# MKL02_Programmer.net
KiCad netlist of a schematic drawn in EAGLE
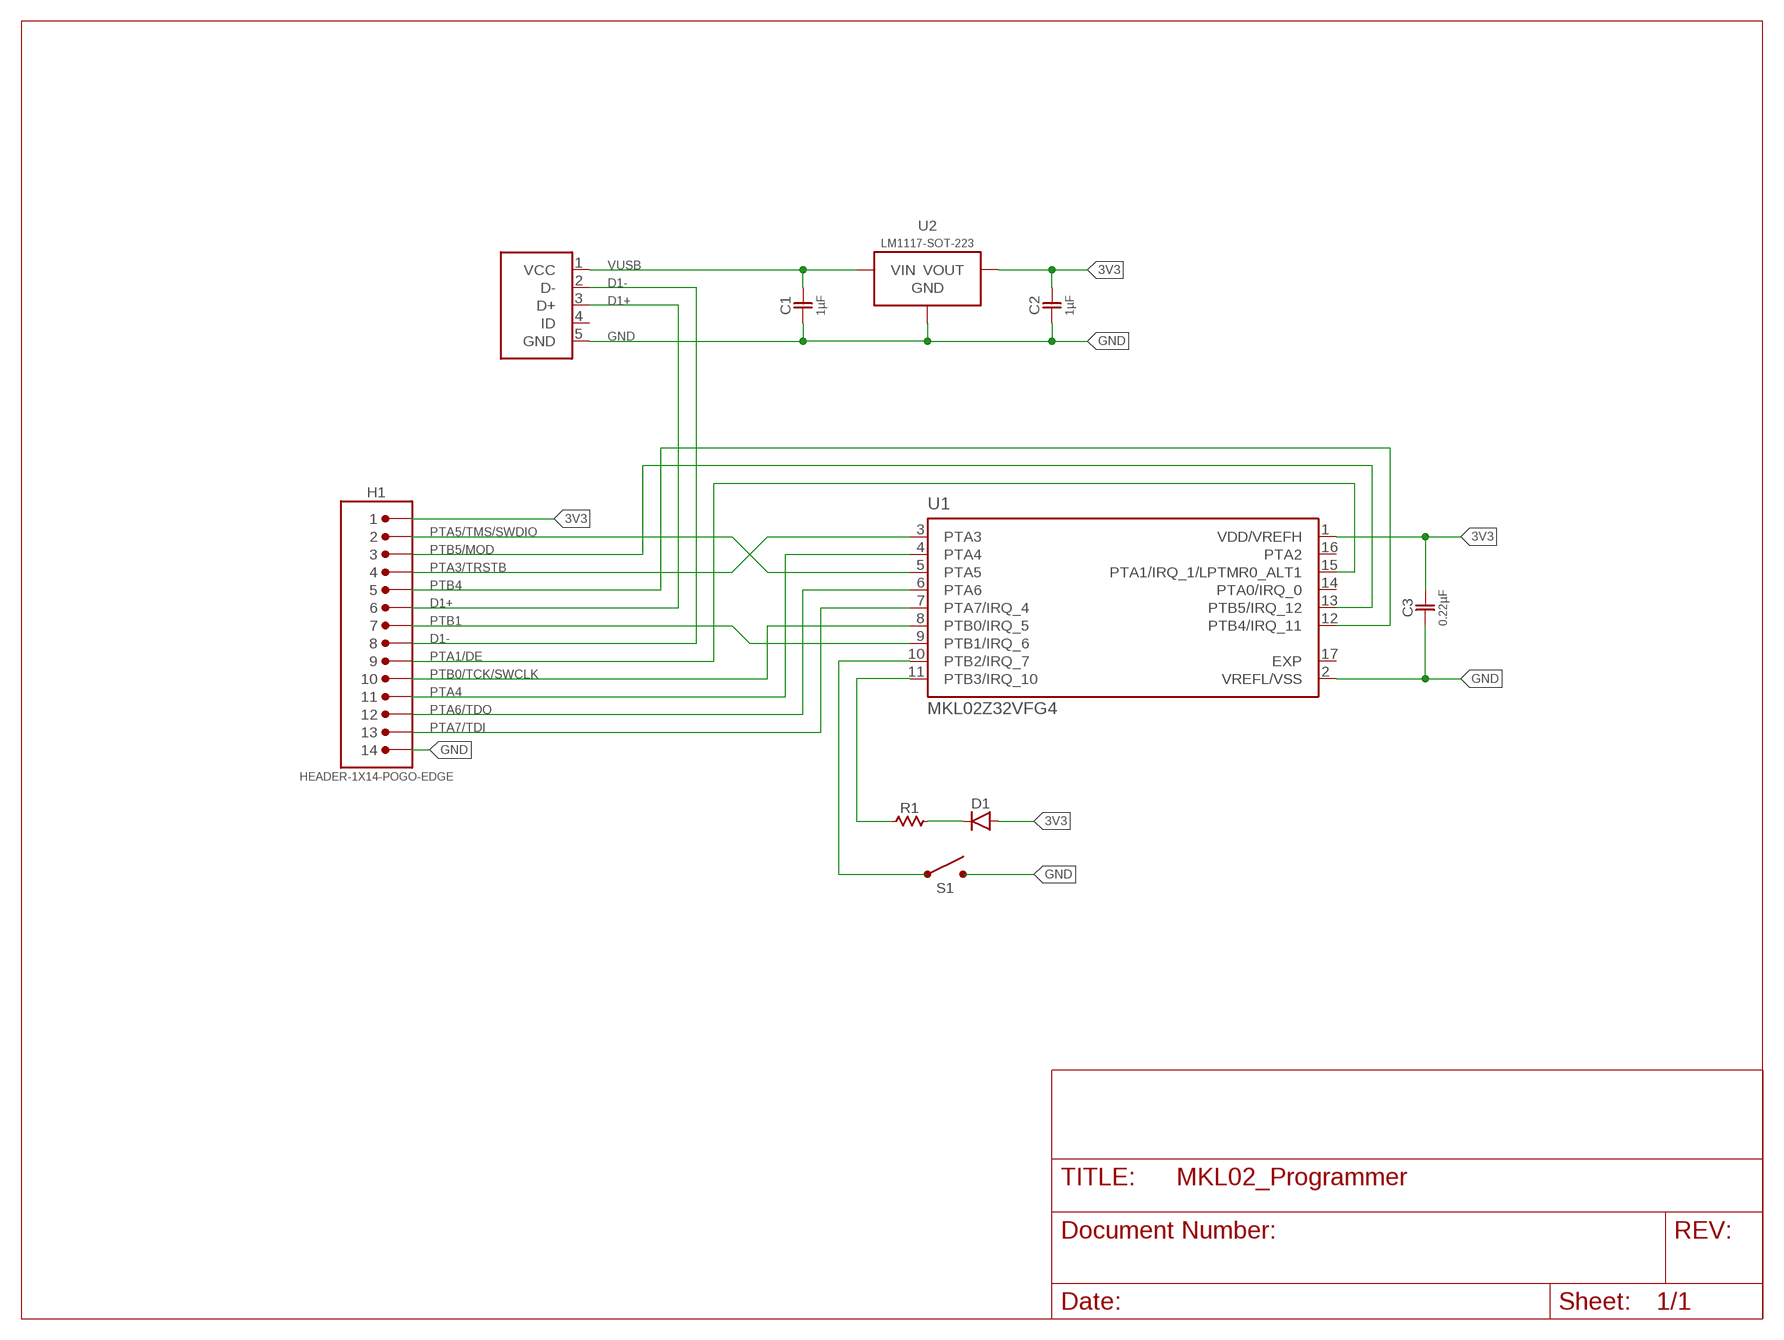
[diagram p0: schematic, sheet 1]

(export (version "E")
  (design (tool "Eeschema 10.0.6"))
  (components
    (comp (ref "C1")
      (value "1µF")
      (footprint "eagle-import:0805-NP")
      (libsource (lib "eagle-import") (part "CAP-NP-0805"))
    )
    (comp (ref "C2")
      (value "1µF")
      (footprint "eagle-import:0805-NP")
      (libsource (lib "eagle-import") (part "CAP-NP-0805"))
    )
    (comp (ref "C3")
      (value "0.22µF")
      (footprint "eagle-import:0805-NP")
      (libsource (lib "eagle-import") (part "CAP-NP-0805"))
    )
    (comp (ref "D1")
      (value "DIODE-0805")
      (footprint "eagle-import:0805-P")
      (libsource (lib "eagle-import") (part "DIODE-0805"))
    )
    (comp (ref "H1")
      (value "HEADER-1X14-POGO-EDGE")
      (footprint "eagle-import:2X7-1.27MM-POGO-EDGE")
      (libsource (lib "eagle-import") (part "HEADER-1X14-POGO-EDGE"))
    )
    (comp (ref "J1")
      (value "USB-5-MICRO-B")
      (footprint "eagle-import:USB-MICRO-B")
      (libsource (lib "eagle-import") (part "USB-5-MICRO-B"))
    )
    (comp (ref "R1")
      (value "RESISTOR-0805")
      (footprint "eagle-import:0805-NP")
      (libsource (lib "eagle-import") (part "RESISTOR-0805"))
    )
    (comp (ref "S1")
      (value "SPST-6X6")
      (footprint "eagle-import:BUTTON-EVQQ2")
      (libsource (lib "eagle-import") (part "SPST-6X6"))
    )
    (comp (ref "U1")
      (value "MKL02Z32VFG4")
      (footprint "eagle-import:QFN50P300X300X65-17N")
      (fields (field (name "DIGI-KEY_PART_NUMBER") "MKL02Z32VFG4-ND") (field (name "MF") "NXP USA"))
      (libsource (lib "eagle-import") (part "MKL02Z32VFG4"))
    )
    (comp (ref "U2")
      (value "LM1117-SOT-223")
      (footprint "eagle-import:SOT-223")
      (libsource (lib "eagle-import") (part "LM1117-SOT-223"))
    )
  )
  (nets
    (net (code "1") (name "/D1+") (class "Default")
      (node (ref "H1") (pin "6") (pinfunction "6_6") (pintype "bidirectional"))
      (node (ref "J1") (pin "3") (pinfunction "D+_3") (pintype "bidirectional"))
    )
    (net (code "2") (name "/D1-") (class "Default")
      (node (ref "H1") (pin "8") (pinfunction "8_8") (pintype "bidirectional"))
      (node (ref "J1") (pin "2") (pinfunction "D-_2") (pintype "bidirectional"))
    )
    (net (code "3") (name "/EXP") (class "Default")
      (node (ref "U1") (pin "17") (pinfunction "EXP_17") (pintype "power_in"))
    )
    (net (code "4") (name "/PTA1{slash}DE") (class "Default")
      (node (ref "H1") (pin "9") (pinfunction "9_9") (pintype "bidirectional"))
      (node (ref "U1") (pin "15") (pinfunction "PTA1/IRQ_1/LPTMR0_ALT1_15") (pintype "bidirectional"))
    )
    (net (code "5") (name "/PTA3{slash}TRSTB") (class "Default")
      (node (ref "H1") (pin "4") (pinfunction "4_4") (pintype "bidirectional"))
      (node (ref "U1") (pin "3") (pinfunction "PTA3_3") (pintype "bidirectional"))
    )
    (net (code "6") (name "/PTA4") (class "Default")
      (node (ref "H1") (pin "11") (pinfunction "11_11") (pintype "bidirectional"))
      (node (ref "U1") (pin "4") (pinfunction "PTA4_4") (pintype "bidirectional"))
    )
    (net (code "7") (name "/PTA5{slash}TMS{slash}SWDIO") (class "Default")
      (node (ref "H1") (pin "2") (pinfunction "2_2") (pintype "bidirectional"))
      (node (ref "U1") (pin "5") (pinfunction "PTA5_5") (pintype "bidirectional"))
    )
    (net (code "8") (name "/PTA6{slash}TDO") (class "Default")
      (node (ref "H1") (pin "12") (pinfunction "12_12") (pintype "bidirectional"))
      (node (ref "U1") (pin "6") (pinfunction "PTA6_6") (pintype "bidirectional"))
    )
    (net (code "9") (name "/PTA7{slash}TDI") (class "Default")
      (node (ref "H1") (pin "13") (pinfunction "13_13") (pintype "bidirectional"))
      (node (ref "U1") (pin "7") (pinfunction "PTA7/IRQ_4_7") (pintype "bidirectional"))
    )
    (net (code "10") (name "/PTB0{slash}TCK{slash}SWCLK") (class "Default")
      (node (ref "H1") (pin "10") (pinfunction "10_10") (pintype "bidirectional"))
      (node (ref "U1") (pin "8") (pinfunction "PTB0/IRQ_5_8") (pintype "bidirectional"))
    )
    (net (code "11") (name "/PTB1") (class "Default")
      (node (ref "H1") (pin "7") (pinfunction "7_7") (pintype "bidirectional"))
      (node (ref "U1") (pin "9") (pinfunction "PTB1/IRQ_6_9") (pintype "bidirectional"))
    )
    (net (code "12") (name "/PTB4") (class "Default")
      (node (ref "H1") (pin "5") (pinfunction "5_5") (pintype "bidirectional"))
      (node (ref "U1") (pin "12") (pinfunction "PTB4/IRQ_11_12") (pintype "bidirectional"))
    )
    (net (code "13") (name "/PTB5{slash}MOD") (class "Default")
      (node (ref "H1") (pin "3") (pinfunction "3_3") (pintype "bidirectional"))
      (node (ref "U1") (pin "13") (pinfunction "PTB5/IRQ_12_13") (pintype "bidirectional"))
    )
    (net (code "14") (name "/VUSB") (class "Default")
      (node (ref "C1") (pin "2") (pinfunction "2_2") (pintype "bidirectional"))
      (node (ref "J1") (pin "1") (pinfunction "VCC_1") (pintype "bidirectional"))
      (node (ref "U2") (pin "3") (pinfunction "VIN_3") (pintype "input"))
    )
    (net (code "15") (name "3V3") (class "Default")
      (node (ref "C2") (pin "2") (pinfunction "2_2") (pintype "bidirectional"))
      (node (ref "C3") (pin "2") (pinfunction "2_2") (pintype "bidirectional"))
      (node (ref "D1") (pin "A") (pinfunction "A_A") (pintype "passive"))
      (node (ref "H1") (pin "1") (pinfunction "1_1") (pintype "bidirectional"))
      (node (ref "U1") (pin "1") (pinfunction "VDD/VREFH_1") (pintype "power_in"))
      (node (ref "U2") (pin "2") (pinfunction "VOUT_2") (pintype "output"))
      (node (ref "U2") (pin "4") (pinfunction "VOUT_4") (pintype "output"))
    )
    (net (code "16") (name "GND") (class "Default")
      (node (ref "C1") (pin "1") (pinfunction "1_1") (pintype "bidirectional"))
      (node (ref "C2") (pin "1") (pinfunction "1_1") (pintype "bidirectional"))
      (node (ref "C3") (pin "1") (pinfunction "1_1") (pintype "bidirectional"))
      (node (ref "H1") (pin "14") (pinfunction "14_14") (pintype "bidirectional"))
      (node (ref "J1") (pin "5") (pinfunction "GND_5") (pintype "bidirectional"))
      (node (ref "S1") (pin "B1") (pinfunction "2_B1") (pintype "bidirectional"))
      (node (ref "S1") (pin "B2") (pinfunction "2_B2") (pintype "bidirectional"))
      (node (ref "U1") (pin "2") (pinfunction "VREFL/VSS_2") (pintype "power_in"))
      (node (ref "U2") (pin "1") (pinfunction "GND_1") (pintype "power_in"))
    )
    (net (code "17") (name "Net-(D1-C)") (class "Default")
      (node (ref "D1") (pin "K") (pinfunction "C_K") (pintype "passive"))
      (node (ref "R1") (pin "2") (pinfunction "2_2") (pintype "passive"))
    )
    (net (code "18") (name "Net-(U1-PTB2{slash}IRQ_7)") (class "Default")
      (node (ref "S1") (pin "A1") (pinfunction "1_A1") (pintype "bidirectional"))
      (node (ref "S1") (pin "A2") (pinfunction "1_A2") (pintype "bidirectional"))
      (node (ref "U1") (pin "10") (pinfunction "PTB2/IRQ_7_10") (pintype "bidirectional"))
    )
    (net (code "19") (name "Net-(U1-PTB3{slash}IRQ_10)") (class "Default")
      (node (ref "R1") (pin "1") (pinfunction "1_1") (pintype "passive"))
      (node (ref "U1") (pin "11") (pinfunction "PTB3/IRQ_10_11") (pintype "bidirectional"))
    )
    (net (code "20") (name "unconnected-(J1-ID-Pad4)") (class "Default")
      (node (ref "J1") (pin "4") (pinfunction "ID_4") (pintype "bidirectional"))
    )
    (net (code "21") (name "unconnected-(U1-PTA0{slash}IRQ_0-Pad14)") (class "Default")
      (node (ref "U1") (pin "14") (pinfunction "PTA0/IRQ_0_14") (pintype "bidirectional"))
    )
    (net (code "22") (name "unconnected-(U1-PTA2-Pad16)") (class "Default")
      (node (ref "U1") (pin "16") (pinfunction "PTA2_16") (pintype "bidirectional"))
    )
  )
)
